# SLC_Free_2_June_29_2017.net
KiCad netlist of a schematic drawn in EAGLE
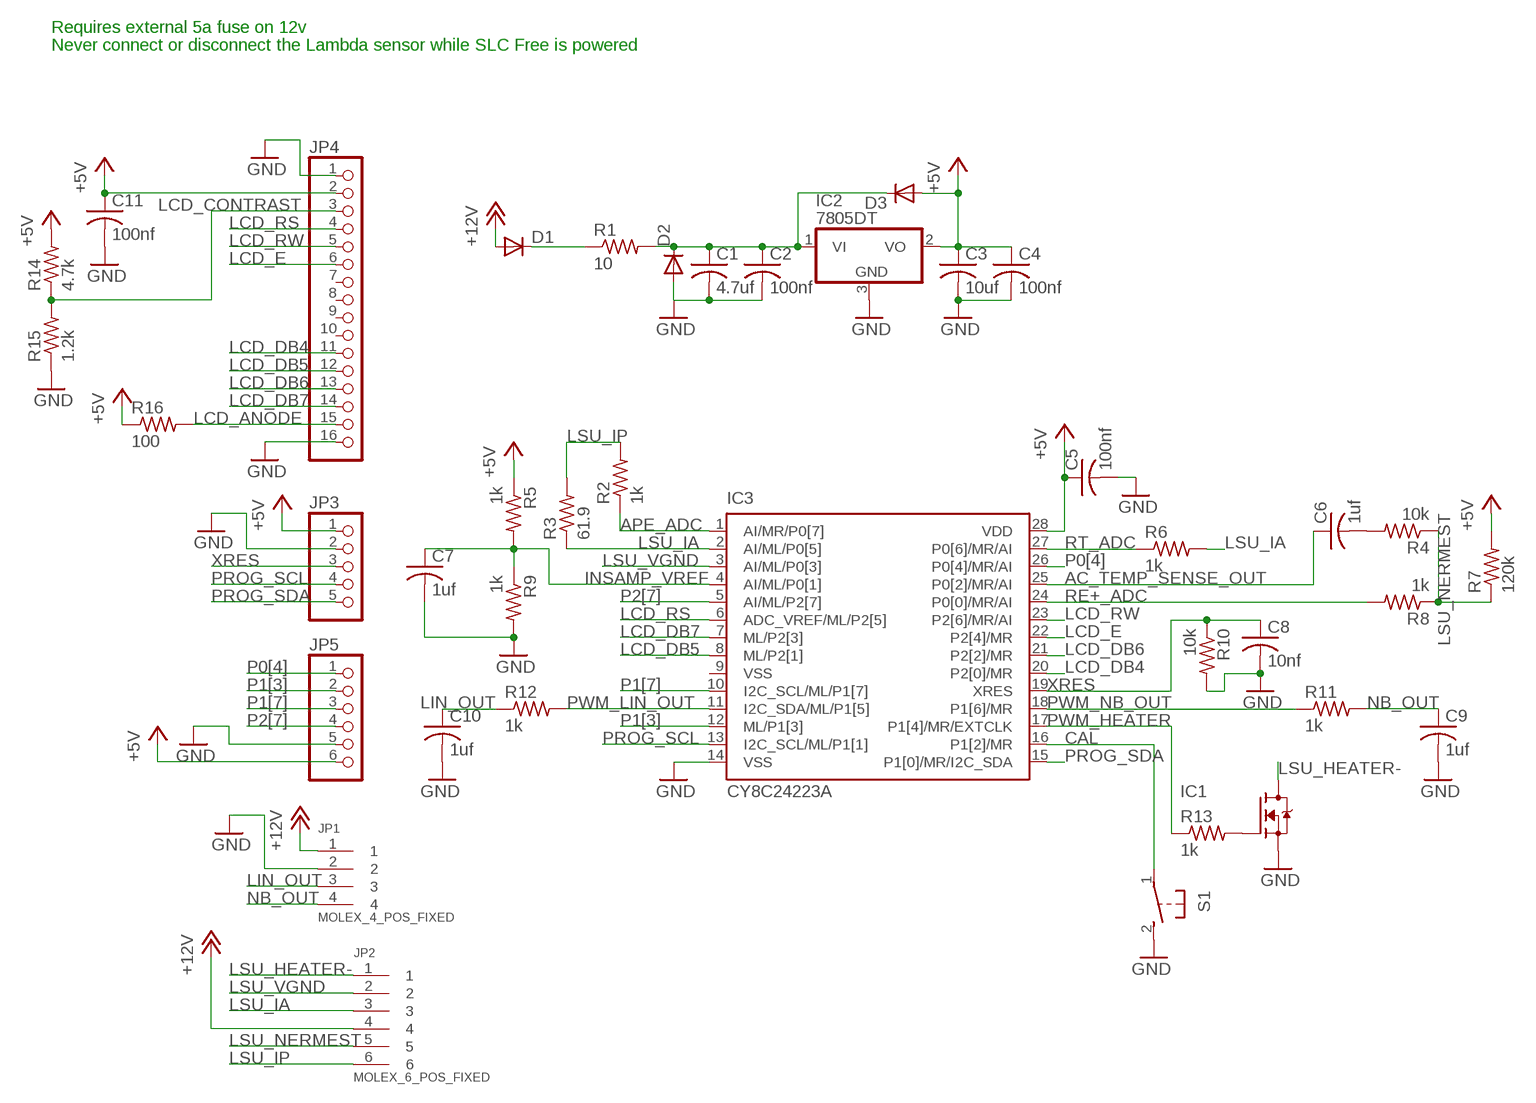
[diagram p0: schematic, sheet 1]

(export (version "E")
  (design (tool "Eeschema 10.0.6"))
  (components
    (comp (ref "C1")
      (value "4.7uf")
      (footprint "eagle-import:C1210")
      (libsource (lib "eagle-import") (part "C-USC1210"))
    )
    (comp (ref "C2")
      (value "100nf")
      (footprint "eagle-import:C0805")
      (libsource (lib "eagle-import") (part "C-USC0805"))
    )
    (comp (ref "C3")
      (value "10uf")
      (footprint "eagle-import:C1206")
      (libsource (lib "eagle-import") (part "C-USC1206"))
    )
    (comp (ref "C4")
      (value "100nf")
      (footprint "eagle-import:C0805")
      (libsource (lib "eagle-import") (part "C-USC0805"))
    )
    (comp (ref "C5")
      (value "100nf")
      (footprint "eagle-import:C0805")
      (libsource (lib "eagle-import") (part "C-USC0805"))
    )
    (comp (ref "C6")
      (value "1uf")
      (footprint "eagle-import:C0805")
      (libsource (lib "eagle-import") (part "C-USC0805"))
    )
    (comp (ref "C7")
      (value "1uf")
      (footprint "eagle-import:C0805")
      (libsource (lib "eagle-import") (part "C-USC0805"))
    )
    (comp (ref "C8")
      (value "10nf")
      (footprint "eagle-import:C0805")
      (libsource (lib "eagle-import") (part "C-USC0805"))
    )
    (comp (ref "C9")
      (value "1uf")
      (footprint "eagle-import:C0805")
      (libsource (lib "eagle-import") (part "C-USC0805"))
    )
    (comp (ref "C10")
      (value "1uf")
      (footprint "eagle-import:C0805")
      (libsource (lib "eagle-import") (part "C-USC0805"))
    )
    (comp (ref "C11")
      (value "100nf")
      (footprint "eagle-import:C0805")
      (libsource (lib "eagle-import") (part "C-USC0805"))
    )
    (comp (ref "D1")
      (value "DIODE-SMB")
      (footprint "eagle-import:SMB")
      (libsource (lib "eagle-import") (part "DIODE-SMB"))
    )
    (comp (ref "D2")
      (value "DIODE-SMB")
      (footprint "eagle-import:SMB")
      (libsource (lib "eagle-import") (part "DIODE-SMB"))
    )
    (comp (ref "D3")
      (value "DIODE-SOD123")
      (footprint "eagle-import:SOD123")
      (libsource (lib "eagle-import") (part "DIODE-SOD123"))
    )
    (comp (ref "IC1")
      (value "FET_NMOS_T0252")
      (footprint "eagle-import:T0252")
      (libsource (lib "eagle-import") (part "FET_NMOS_T0252"))
    )
    (comp (ref "IC2")
      (value "7805DT")
      (footprint "eagle-import:TO252")
      (libsource (lib "eagle-import") (part "78DT05"))
    )
    (comp (ref "IC3")
      (value "CY8C24223A")
      (footprint "eagle-import:SSOP28")
      (libsource (lib "eagle-import") (part "CY8C24223A"))
    )
    (comp (ref "JP1")
      (value "MOLEX_4_POS_FIXED")
      (footprint "eagle-import:MOLEX_4_POS_FIXED")
      (libsource (lib "eagle-import") (part "MOLEX_4_POS_FIXED"))
    )
    (comp (ref "JP2")
      (value "MOLEX_6_POS_FIXED")
      (footprint "eagle-import:MOLEX_6_POS_FIXED")
      (libsource (lib "eagle-import") (part "MOLEX_6_POS_FIXED"))
    )
    (comp (ref "JP3")
      (value "PINHD-1X5")
      (footprint "eagle-import:1X05")
      (libsource (lib "eagle-import") (part "PINHD-1X5"))
    )
    (comp (ref "JP4")
      (value "PINHD-1X16")
      (footprint "eagle-import:1X16")
      (libsource (lib "eagle-import") (part "PINHD-1X16"))
    )
    (comp (ref "JP5")
      (value "PINHD-1X6")
      (footprint "eagle-import:1X06")
      (libsource (lib "eagle-import") (part "PINHD-1X6"))
    )
    (comp (ref "R1")
      (value "10")
      (footprint "eagle-import:R1206")
      (libsource (lib "eagle-import") (part "R-US_R1206"))
    )
    (comp (ref "R2")
      (value "1k")
      (footprint "eagle-import:R0805")
      (libsource (lib "eagle-import") (part "R-US_R0805"))
    )
    (comp (ref "R3")
      (value "61.9")
      (footprint "eagle-import:R0805")
      (libsource (lib "eagle-import") (part "R-US_R0805"))
    )
    (comp (ref "R4")
      (value "10k")
      (footprint "eagle-import:R0805")
      (libsource (lib "eagle-import") (part "R-US_R0805"))
    )
    (comp (ref "R5")
      (value "1k")
      (footprint "eagle-import:R0805")
      (libsource (lib "eagle-import") (part "R-US_R0805"))
    )
    (comp (ref "R6")
      (value "1k")
      (footprint "eagle-import:R0805")
      (libsource (lib "eagle-import") (part "R-US_R0805"))
    )
    (comp (ref "R7")
      (value "120k")
      (footprint "eagle-import:R0805")
      (libsource (lib "eagle-import") (part "R-US_R0805"))
    )
    (comp (ref "R8")
      (value "1k")
      (footprint "eagle-import:R0805")
      (libsource (lib "eagle-import") (part "R-US_R0805"))
    )
    (comp (ref "R9")
      (value "1k")
      (footprint "eagle-import:R0805")
      (libsource (lib "eagle-import") (part "R-US_R0805"))
    )
    (comp (ref "R10")
      (value "10k")
      (footprint "eagle-import:R0805")
      (libsource (lib "eagle-import") (part "R-US_R0805"))
    )
    (comp (ref "R11")
      (value "1k")
      (footprint "eagle-import:R0805")
      (libsource (lib "eagle-import") (part "R-US_R0805"))
    )
    (comp (ref "R12")
      (value "1k")
      (footprint "eagle-import:R0805")
      (libsource (lib "eagle-import") (part "R-US_R0805"))
    )
    (comp (ref "R13")
      (value "1k")
      (footprint "eagle-import:R0805")
      (libsource (lib "eagle-import") (part "R-US_R0805"))
    )
    (comp (ref "R14")
      (value "4.7k")
      (footprint "eagle-import:R0805")
      (libsource (lib "eagle-import") (part "R-US_R0805"))
    )
    (comp (ref "R15")
      (value "1.2k")
      (footprint "eagle-import:R0805")
      (libsource (lib "eagle-import") (part "R-US_R0805"))
    )
    (comp (ref "R16")
      (value "100")
      (footprint "eagle-import:R1206")
      (libsource (lib "eagle-import") (part "R-US_R1206"))
    )
    (comp (ref "S1")
      (value "31-XX")
      (footprint "eagle-import:B3F-31XX")
      (fields (field (name "MPN") "B3F-3100"))
      (libsource (lib "eagle-import") (part "31-XX"))
    )
  )
  (nets
    (net (code "1") (name "+5V") (class "Default")
      (node (ref "C11") (pin "1") (pinfunction "1_1") (pintype "passive"))
      (node (ref "C3") (pin "1") (pinfunction "1_1") (pintype "passive"))
      (node (ref "C4") (pin "1") (pinfunction "1_1") (pintype "passive"))
      (node (ref "C5") (pin "1") (pinfunction "1_1") (pintype "passive"))
      (node (ref "D3") (pin "A") (pinfunction "A_A") (pintype "passive"))
      (node (ref "IC2") (pin "2") (pinfunction "VO_2") (pintype "passive"))
      (node (ref "IC3") (pin "28") (pinfunction "VDD_28") (pintype "power_in"))
      (node (ref "JP3") (pin "1") (pinfunction "1_1") (pintype "passive"))
      (node (ref "JP4") (pin "2") (pinfunction "2_2") (pintype "passive"))
      (node (ref "JP5") (pin "6") (pinfunction "6_6") (pintype "passive"))
      (node (ref "R14") (pin "2") (pinfunction "2_2") (pintype "passive"))
      (node (ref "R16") (pin "1") (pinfunction "1_1") (pintype "passive"))
      (node (ref "R5") (pin "1") (pinfunction "1_1") (pintype "passive"))
      (node (ref "R7") (pin "2") (pinfunction "2_2") (pintype "passive"))
    )
    (net (code "2") (name "+12V") (class "Default")
      (node (ref "D1") (pin "A") (pinfunction "A_A") (pintype "passive"))
      (node (ref "JP1") (pin "1") (pinfunction "1_1") (pintype "bidirectional"))
      (node (ref "JP2") (pin "4") (pinfunction "4_4") (pintype "bidirectional"))
    )
    (net (code "3") (name "/AC_TEMP_SENSE_OUT") (class "Default")
      (node (ref "C6") (pin "1") (pinfunction "1_1") (pintype "passive"))
      (node (ref "IC3") (pin "25") (pinfunction "P0[2]/MR/AI_25") (pintype "bidirectional"))
    )
    (net (code "4") (name "/APE_ADC") (class "Default")
      (node (ref "IC3") (pin "1") (pinfunction "AI/MR/P0[7]_1") (pintype "bidirectional"))
      (node (ref "R2") (pin "1") (pinfunction "1_1") (pintype "passive"))
    )
    (net (code "5") (name "/CAL") (class "Default")
      (node (ref "IC3") (pin "16") (pinfunction "P1[2]/MR_16") (pintype "bidirectional"))
      (node (ref "S1") (pin "1") (pinfunction "P_1") (pintype "passive"))
    )
    (net (code "6") (name "/INSAMP_VREF") (class "Default")
      (node (ref "C7") (pin "1") (pinfunction "1_1") (pintype "passive"))
      (node (ref "IC3") (pin "4") (pinfunction "AI/ML/P0[1]_4") (pintype "bidirectional"))
      (node (ref "R5") (pin "2") (pinfunction "2_2") (pintype "passive"))
      (node (ref "R9") (pin "1") (pinfunction "1_1") (pintype "passive"))
    )
    (net (code "7") (name "/LCD_ANODE") (class "Default")
      (node (ref "JP4") (pin "15") (pinfunction "15_15") (pintype "passive"))
      (node (ref "R16") (pin "2") (pinfunction "2_2") (pintype "passive"))
    )
    (net (code "8") (name "/LCD_CONTRAST") (class "Default")
      (node (ref "JP4") (pin "3") (pinfunction "3_3") (pintype "passive"))
      (node (ref "R14") (pin "1") (pinfunction "1_1") (pintype "passive"))
      (node (ref "R15") (pin "2") (pinfunction "2_2") (pintype "passive"))
    )
    (net (code "9") (name "/LCD_DB4") (class "Default")
      (node (ref "IC3") (pin "20") (pinfunction "P2[0]/MR_20") (pintype "bidirectional"))
      (node (ref "JP4") (pin "11") (pinfunction "11_11") (pintype "passive"))
    )
    (net (code "10") (name "/LCD_DB5") (class "Default")
      (node (ref "IC3") (pin "8") (pinfunction "ML/P2[1]_8") (pintype "bidirectional"))
      (node (ref "JP4") (pin "12") (pinfunction "12_12") (pintype "passive"))
    )
    (net (code "11") (name "/LCD_DB6") (class "Default")
      (node (ref "IC3") (pin "21") (pinfunction "P2[2]/MR_21") (pintype "bidirectional"))
      (node (ref "JP4") (pin "13") (pinfunction "13_13") (pintype "passive"))
    )
    (net (code "12") (name "/LCD_DB7") (class "Default")
      (node (ref "IC3") (pin "7") (pinfunction "ML/P2[3]_7") (pintype "bidirectional"))
      (node (ref "JP4") (pin "14") (pinfunction "14_14") (pintype "passive"))
    )
    (net (code "13") (name "/LCD_E") (class "Default")
      (node (ref "IC3") (pin "22") (pinfunction "P2[4]/MR_22") (pintype "bidirectional"))
      (node (ref "JP4") (pin "6") (pinfunction "6_6") (pintype "passive"))
    )
    (net (code "14") (name "/LCD_RS") (class "Default")
      (node (ref "IC3") (pin "6") (pinfunction "ADC_VREF/ML/P2[5]_6") (pintype "bidirectional"))
      (node (ref "JP4") (pin "4") (pinfunction "4_4") (pintype "passive"))
    )
    (net (code "15") (name "/LCD_RW") (class "Default")
      (node (ref "IC3") (pin "23") (pinfunction "P2[6]/MR/AI_23") (pintype "bidirectional"))
      (node (ref "JP4") (pin "5") (pinfunction "5_5") (pintype "passive"))
    )
    (net (code "16") (name "/LIN_OUT") (class "Default")
      (node (ref "C10") (pin "1") (pinfunction "1_1") (pintype "passive"))
      (node (ref "JP1") (pin "3") (pinfunction "3_3") (pintype "bidirectional"))
      (node (ref "R12") (pin "1") (pinfunction "1_1") (pintype "passive"))
    )
    (net (code "17") (name "/LSU_HEATER-") (class "Default")
      (node (ref "IC1") (pin "3") (pinfunction "D_3") (pintype "passive"))
      (node (ref "JP2") (pin "1") (pinfunction "1_1") (pintype "bidirectional"))
    )
    (net (code "18") (name "/LSU_IA") (class "Default")
      (node (ref "IC3") (pin "2") (pinfunction "AI/ML/P0[5]_2") (pintype "bidirectional"))
      (node (ref "JP2") (pin "3") (pinfunction "3_3") (pintype "bidirectional"))
      (node (ref "R3") (pin "1") (pinfunction "1_1") (pintype "passive"))
      (node (ref "R6") (pin "2") (pinfunction "2_2") (pintype "passive"))
    )
    (net (code "19") (name "/LSU_IP") (class "Default")
      (node (ref "JP2") (pin "6") (pinfunction "6_6") (pintype "bidirectional"))
      (node (ref "R2") (pin "2") (pinfunction "2_2") (pintype "passive"))
      (node (ref "R3") (pin "2") (pinfunction "2_2") (pintype "passive"))
    )
    (net (code "20") (name "/LSU_NERMEST") (class "Default")
      (node (ref "JP2") (pin "5") (pinfunction "5_5") (pintype "bidirectional"))
      (node (ref "R4") (pin "1") (pinfunction "1_1") (pintype "passive"))
      (node (ref "R7") (pin "1") (pinfunction "1_1") (pintype "passive"))
      (node (ref "R8") (pin "1") (pinfunction "1_1") (pintype "passive"))
    )
    (net (code "21") (name "/LSU_VGND") (class "Default")
      (node (ref "IC3") (pin "3") (pinfunction "AI/ML/P0[3]_3") (pintype "bidirectional"))
      (node (ref "JP2") (pin "2") (pinfunction "2_2") (pintype "bidirectional"))
    )
    (net (code "22") (name "/NB_OUT") (class "Default")
      (node (ref "C9") (pin "1") (pinfunction "1_1") (pintype "passive"))
      (node (ref "JP1") (pin "4") (pinfunction "4_4") (pintype "bidirectional"))
      (node (ref "R11") (pin "2") (pinfunction "2_2") (pintype "passive"))
    )
    (net (code "23") (name "/P0[4]") (class "Default")
      (node (ref "IC3") (pin "26") (pinfunction "P0[4]/MR/AI_26") (pintype "bidirectional"))
      (node (ref "JP5") (pin "1") (pinfunction "1_1") (pintype "passive"))
    )
    (net (code "24") (name "/P1[3]") (class "Default")
      (node (ref "IC3") (pin "12") (pinfunction "ML/P1[3]_12") (pintype "bidirectional"))
      (node (ref "JP5") (pin "2") (pinfunction "2_2") (pintype "passive"))
    )
    (net (code "25") (name "/P1[7]") (class "Default")
      (node (ref "IC3") (pin "10") (pinfunction "I2C_SCL/ML/P1[7]_10") (pintype "bidirectional"))
      (node (ref "JP5") (pin "3") (pinfunction "3_3") (pintype "passive"))
    )
    (net (code "26") (name "/P2[7]") (class "Default")
      (node (ref "IC3") (pin "5") (pinfunction "AI/ML/P2[7]_5") (pintype "bidirectional"))
      (node (ref "JP5") (pin "4") (pinfunction "4_4") (pintype "passive"))
    )
    (net (code "27") (name "/PROG_SCL") (class "Default")
      (node (ref "IC3") (pin "13") (pinfunction "I2C_SCL/ML/P1[1]_13") (pintype "bidirectional"))
      (node (ref "JP3") (pin "4") (pinfunction "4_4") (pintype "passive"))
    )
    (net (code "28") (name "/PROG_SDA") (class "Default")
      (node (ref "IC3") (pin "15") (pinfunction "P1[0]/MR/I2C_SDA_15") (pintype "bidirectional"))
      (node (ref "JP3") (pin "5") (pinfunction "5_5") (pintype "passive"))
    )
    (net (code "29") (name "/PWM_HEATER") (class "Default")
      (node (ref "IC3") (pin "17") (pinfunction "P1[4]/MR/EXTCLK_17") (pintype "bidirectional"))
      (node (ref "R13") (pin "1") (pinfunction "1_1") (pintype "passive"))
    )
    (net (code "30") (name "/PWM_LIN_OUT") (class "Default")
      (node (ref "IC3") (pin "11") (pinfunction "I2C_SDA/ML/P1[5]_11") (pintype "bidirectional"))
      (node (ref "R12") (pin "2") (pinfunction "2_2") (pintype "passive"))
    )
    (net (code "31") (name "/PWM_NB_OUT") (class "Default")
      (node (ref "IC3") (pin "18") (pinfunction "P1[6]/MR_18") (pintype "bidirectional"))
      (node (ref "R11") (pin "1") (pinfunction "1_1") (pintype "passive"))
    )
    (net (code "32") (name "/RE+_ADC") (class "Default")
      (node (ref "IC3") (pin "24") (pinfunction "P0[0]/MR/AI_24") (pintype "bidirectional"))
      (node (ref "R8") (pin "2") (pinfunction "2_2") (pintype "passive"))
    )
    (net (code "33") (name "/RT_ADC") (class "Default")
      (node (ref "IC3") (pin "27") (pinfunction "P0[6]/MR/AI_27") (pintype "bidirectional"))
      (node (ref "R6") (pin "1") (pinfunction "1_1") (pintype "passive"))
    )
    (net (code "34") (name "/VSS") (class "Default")
      (node (ref "IC3") (pin "9") (pinfunction "VSS_9") (pintype "power_in"))
    )
    (net (code "35") (name "/XRES") (class "Default")
      (node (ref "C8") (pin "1") (pinfunction "1_1") (pintype "passive"))
      (node (ref "IC3") (pin "19") (pinfunction "XRES_19") (pintype "input"))
      (node (ref "JP3") (pin "3") (pinfunction "3_3") (pintype "passive"))
      (node (ref "R10") (pin "1") (pinfunction "1_1") (pintype "passive"))
    )
    (net (code "36") (name "GND") (class "Default")
      (node (ref "C1") (pin "2") (pinfunction "2_2") (pintype "passive"))
      (node (ref "C10") (pin "2") (pinfunction "2_2") (pintype "passive"))
      (node (ref "C11") (pin "2") (pinfunction "2_2") (pintype "passive"))
      (node (ref "C2") (pin "2") (pinfunction "2_2") (pintype "passive"))
      (node (ref "C3") (pin "2") (pinfunction "2_2") (pintype "passive"))
      (node (ref "C4") (pin "2") (pinfunction "2_2") (pintype "passive"))
      (node (ref "C5") (pin "2") (pinfunction "2_2") (pintype "passive"))
      (node (ref "C7") (pin "2") (pinfunction "2_2") (pintype "passive"))
      (node (ref "C8") (pin "2") (pinfunction "2_2") (pintype "passive"))
      (node (ref "C9") (pin "2") (pinfunction "2_2") (pintype "passive"))
      (node (ref "D2") (pin "A") (pinfunction "A_A") (pintype "passive"))
      (node (ref "IC1") (pin "2") (pinfunction "S_2") (pintype "passive"))
      (node (ref "IC2") (pin "3") (pinfunction "GND_3") (pintype "passive"))
      (node (ref "IC3") (pin "14") (pinfunction "VSS_14") (pintype "power_in"))
      (node (ref "JP1") (pin "2") (pinfunction "2_2") (pintype "bidirectional"))
      (node (ref "JP3") (pin "2") (pinfunction "2_2") (pintype "passive"))
      (node (ref "JP4") (pin "1") (pinfunction "1_1") (pintype "passive"))
      (node (ref "JP4") (pin "16") (pinfunction "16_16") (pintype "passive"))
      (node (ref "JP5") (pin "5") (pinfunction "5_5") (pintype "passive"))
      (node (ref "R10") (pin "2") (pinfunction "2_2") (pintype "passive"))
      (node (ref "R15") (pin "1") (pinfunction "1_1") (pintype "passive"))
      (node (ref "R9") (pin "2") (pinfunction "2_2") (pintype "passive"))
      (node (ref "S1") (pin "2") (pinfunction "S_2") (pintype "passive"))
    )
    (net (code "37") (name "Net-(C6-Pad2)") (class "Default")
      (node (ref "C6") (pin "2") (pinfunction "2_2") (pintype "passive"))
      (node (ref "R4") (pin "2") (pinfunction "2_2") (pintype "passive"))
    )
    (net (code "38") (name "Net-(D1-PadC)") (class "Default")
      (node (ref "D1") (pin "C") (pinfunction "C_C") (pintype "passive"))
      (node (ref "R1") (pin "1") (pinfunction "1_1") (pintype "passive"))
    )
    (net (code "39") (name "Net-(IC1-G)") (class "Default")
      (node (ref "IC1") (pin "1") (pinfunction "G_1") (pintype "passive"))
      (node (ref "R13") (pin "2") (pinfunction "2_2") (pintype "passive"))
    )
    (net (code "40") (name "Net-(IC2-VI)") (class "Default")
      (node (ref "C1") (pin "1") (pinfunction "1_1") (pintype "passive"))
      (node (ref "C2") (pin "1") (pinfunction "1_1") (pintype "passive"))
      (node (ref "D2") (pin "C") (pinfunction "C_C") (pintype "passive"))
      (node (ref "D3") (pin "C") (pinfunction "C_C") (pintype "passive"))
      (node (ref "IC2") (pin "1") (pinfunction "VI_1") (pintype "input"))
      (node (ref "R1") (pin "2") (pinfunction "2_2") (pintype "passive"))
    )
    (net (code "41") (name "unconnected-(JP4-Pad7)") (class "Default")
      (node (ref "JP4") (pin "7") (pinfunction "7_7") (pintype "passive"))
    )
    (net (code "42") (name "unconnected-(JP4-Pad8)") (class "Default")
      (node (ref "JP4") (pin "8") (pinfunction "8_8") (pintype "passive"))
    )
    (net (code "43") (name "unconnected-(JP4-Pad9)") (class "Default")
      (node (ref "JP4") (pin "9") (pinfunction "9_9") (pintype "passive"))
    )
    (net (code "44") (name "unconnected-(JP4-Pad10)") (class "Default")
      (node (ref "JP4") (pin "10") (pinfunction "10_10") (pintype "passive"))
    )
  )
)
